# PT_2015_DB_MAIN_Rev1.net
KiCad netlist of a schematic drawn in EAGLE
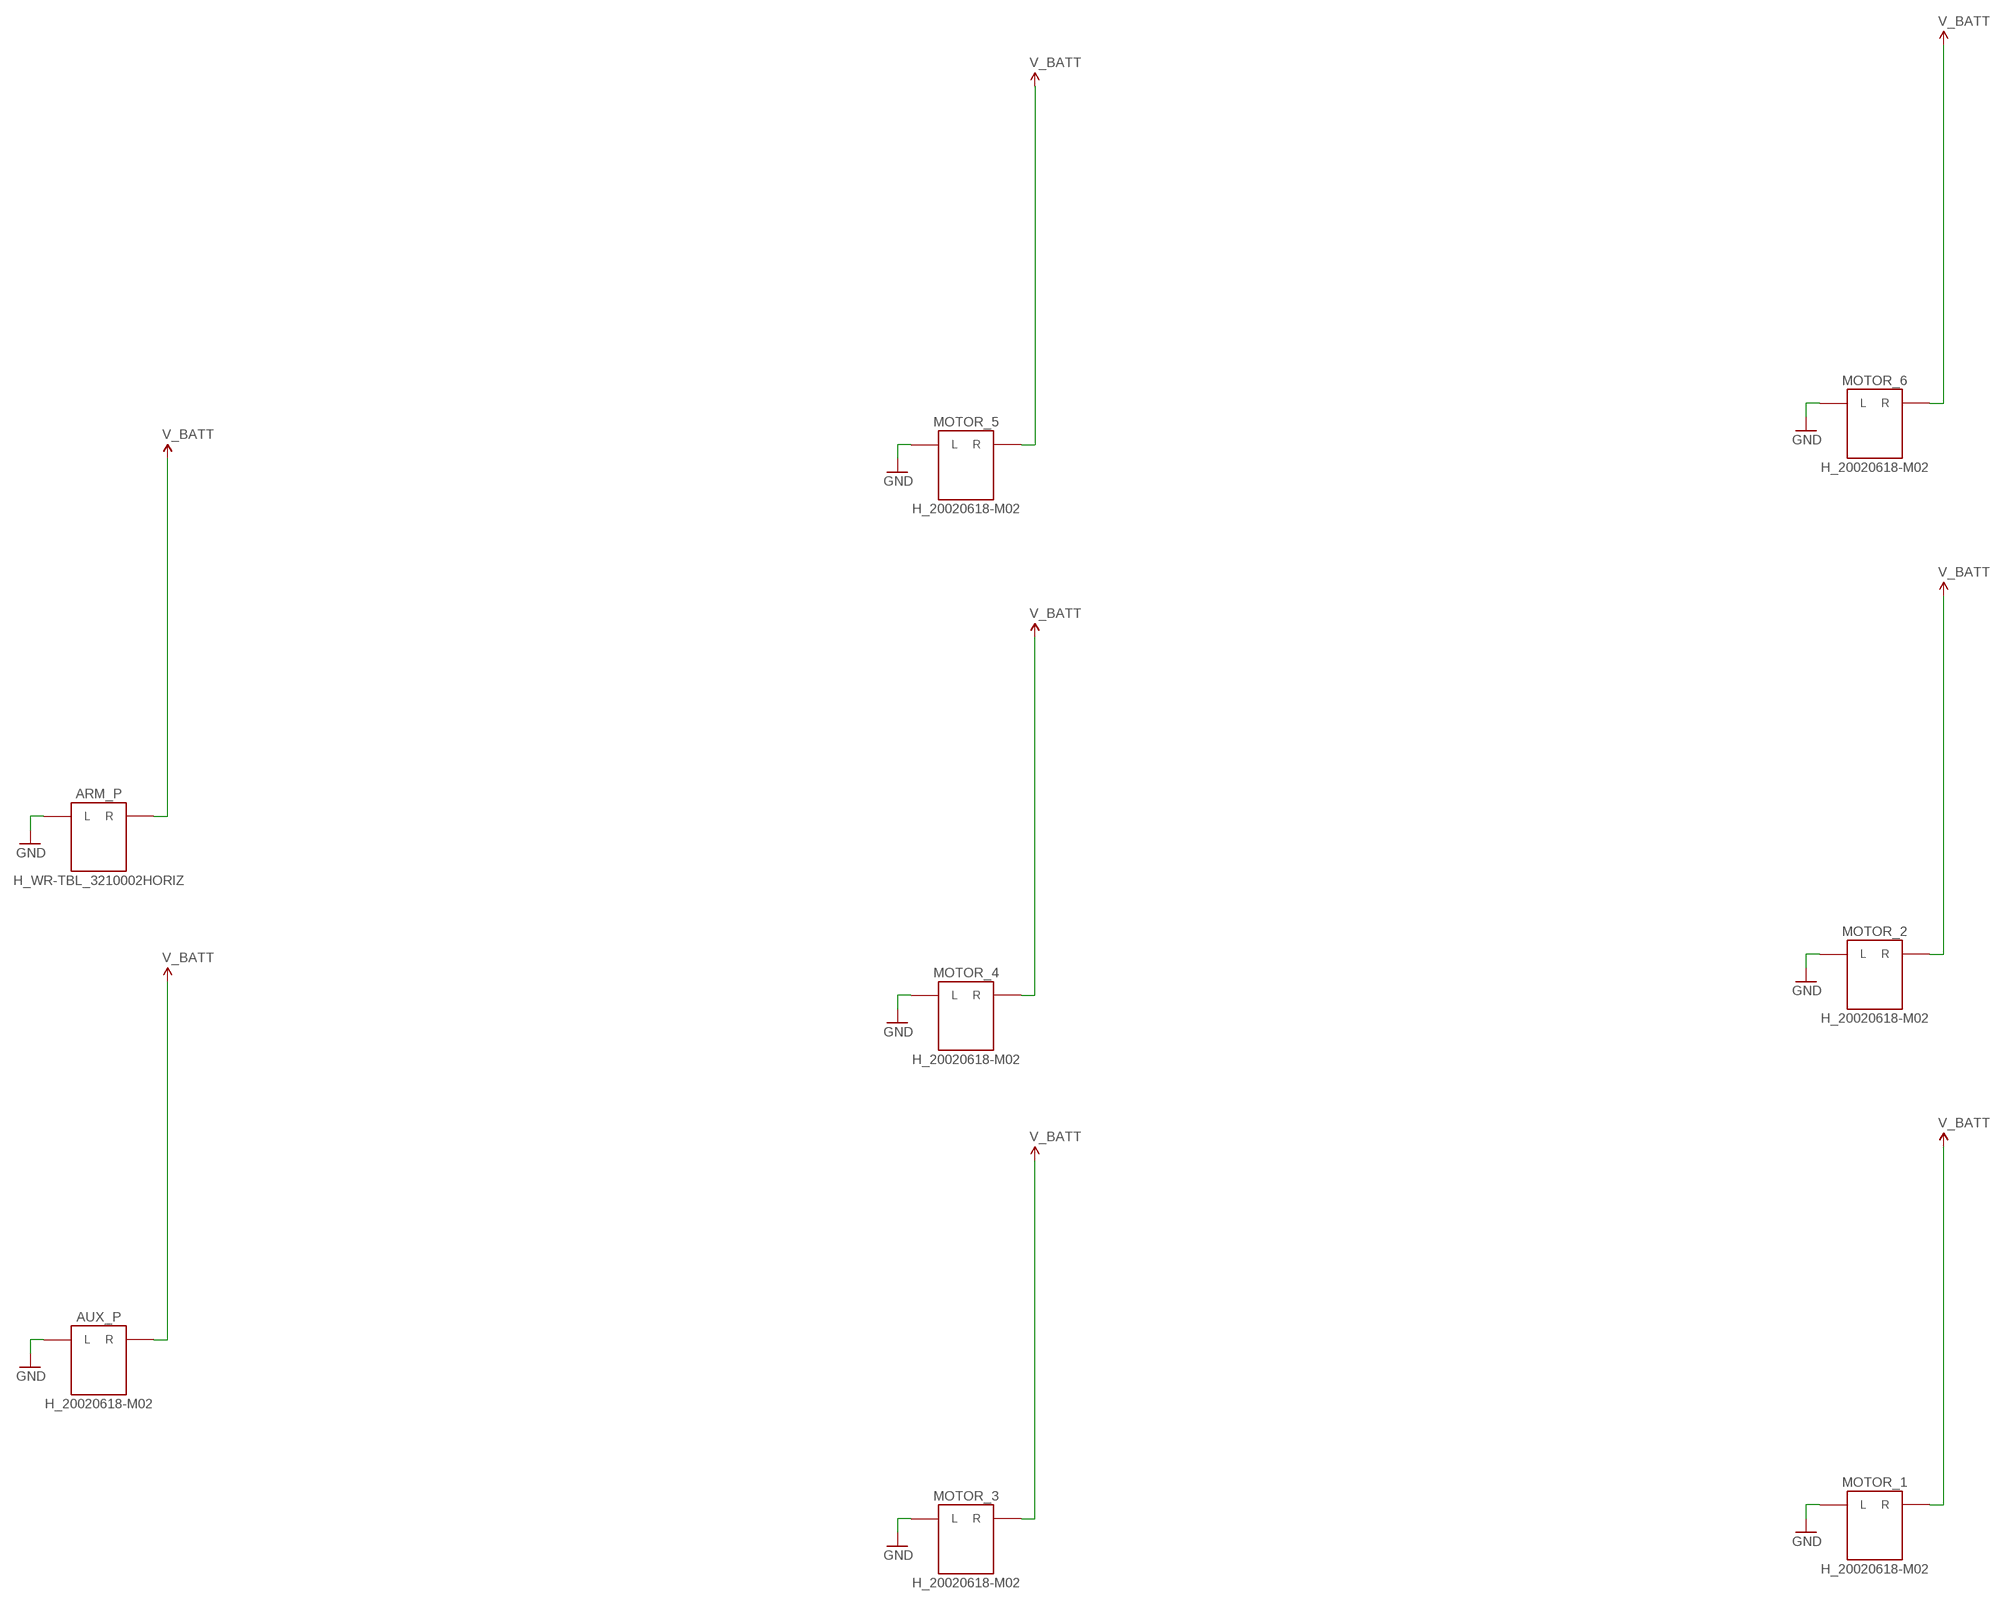
[diagram p0: schematic, sheet 1, part 1 of 2]
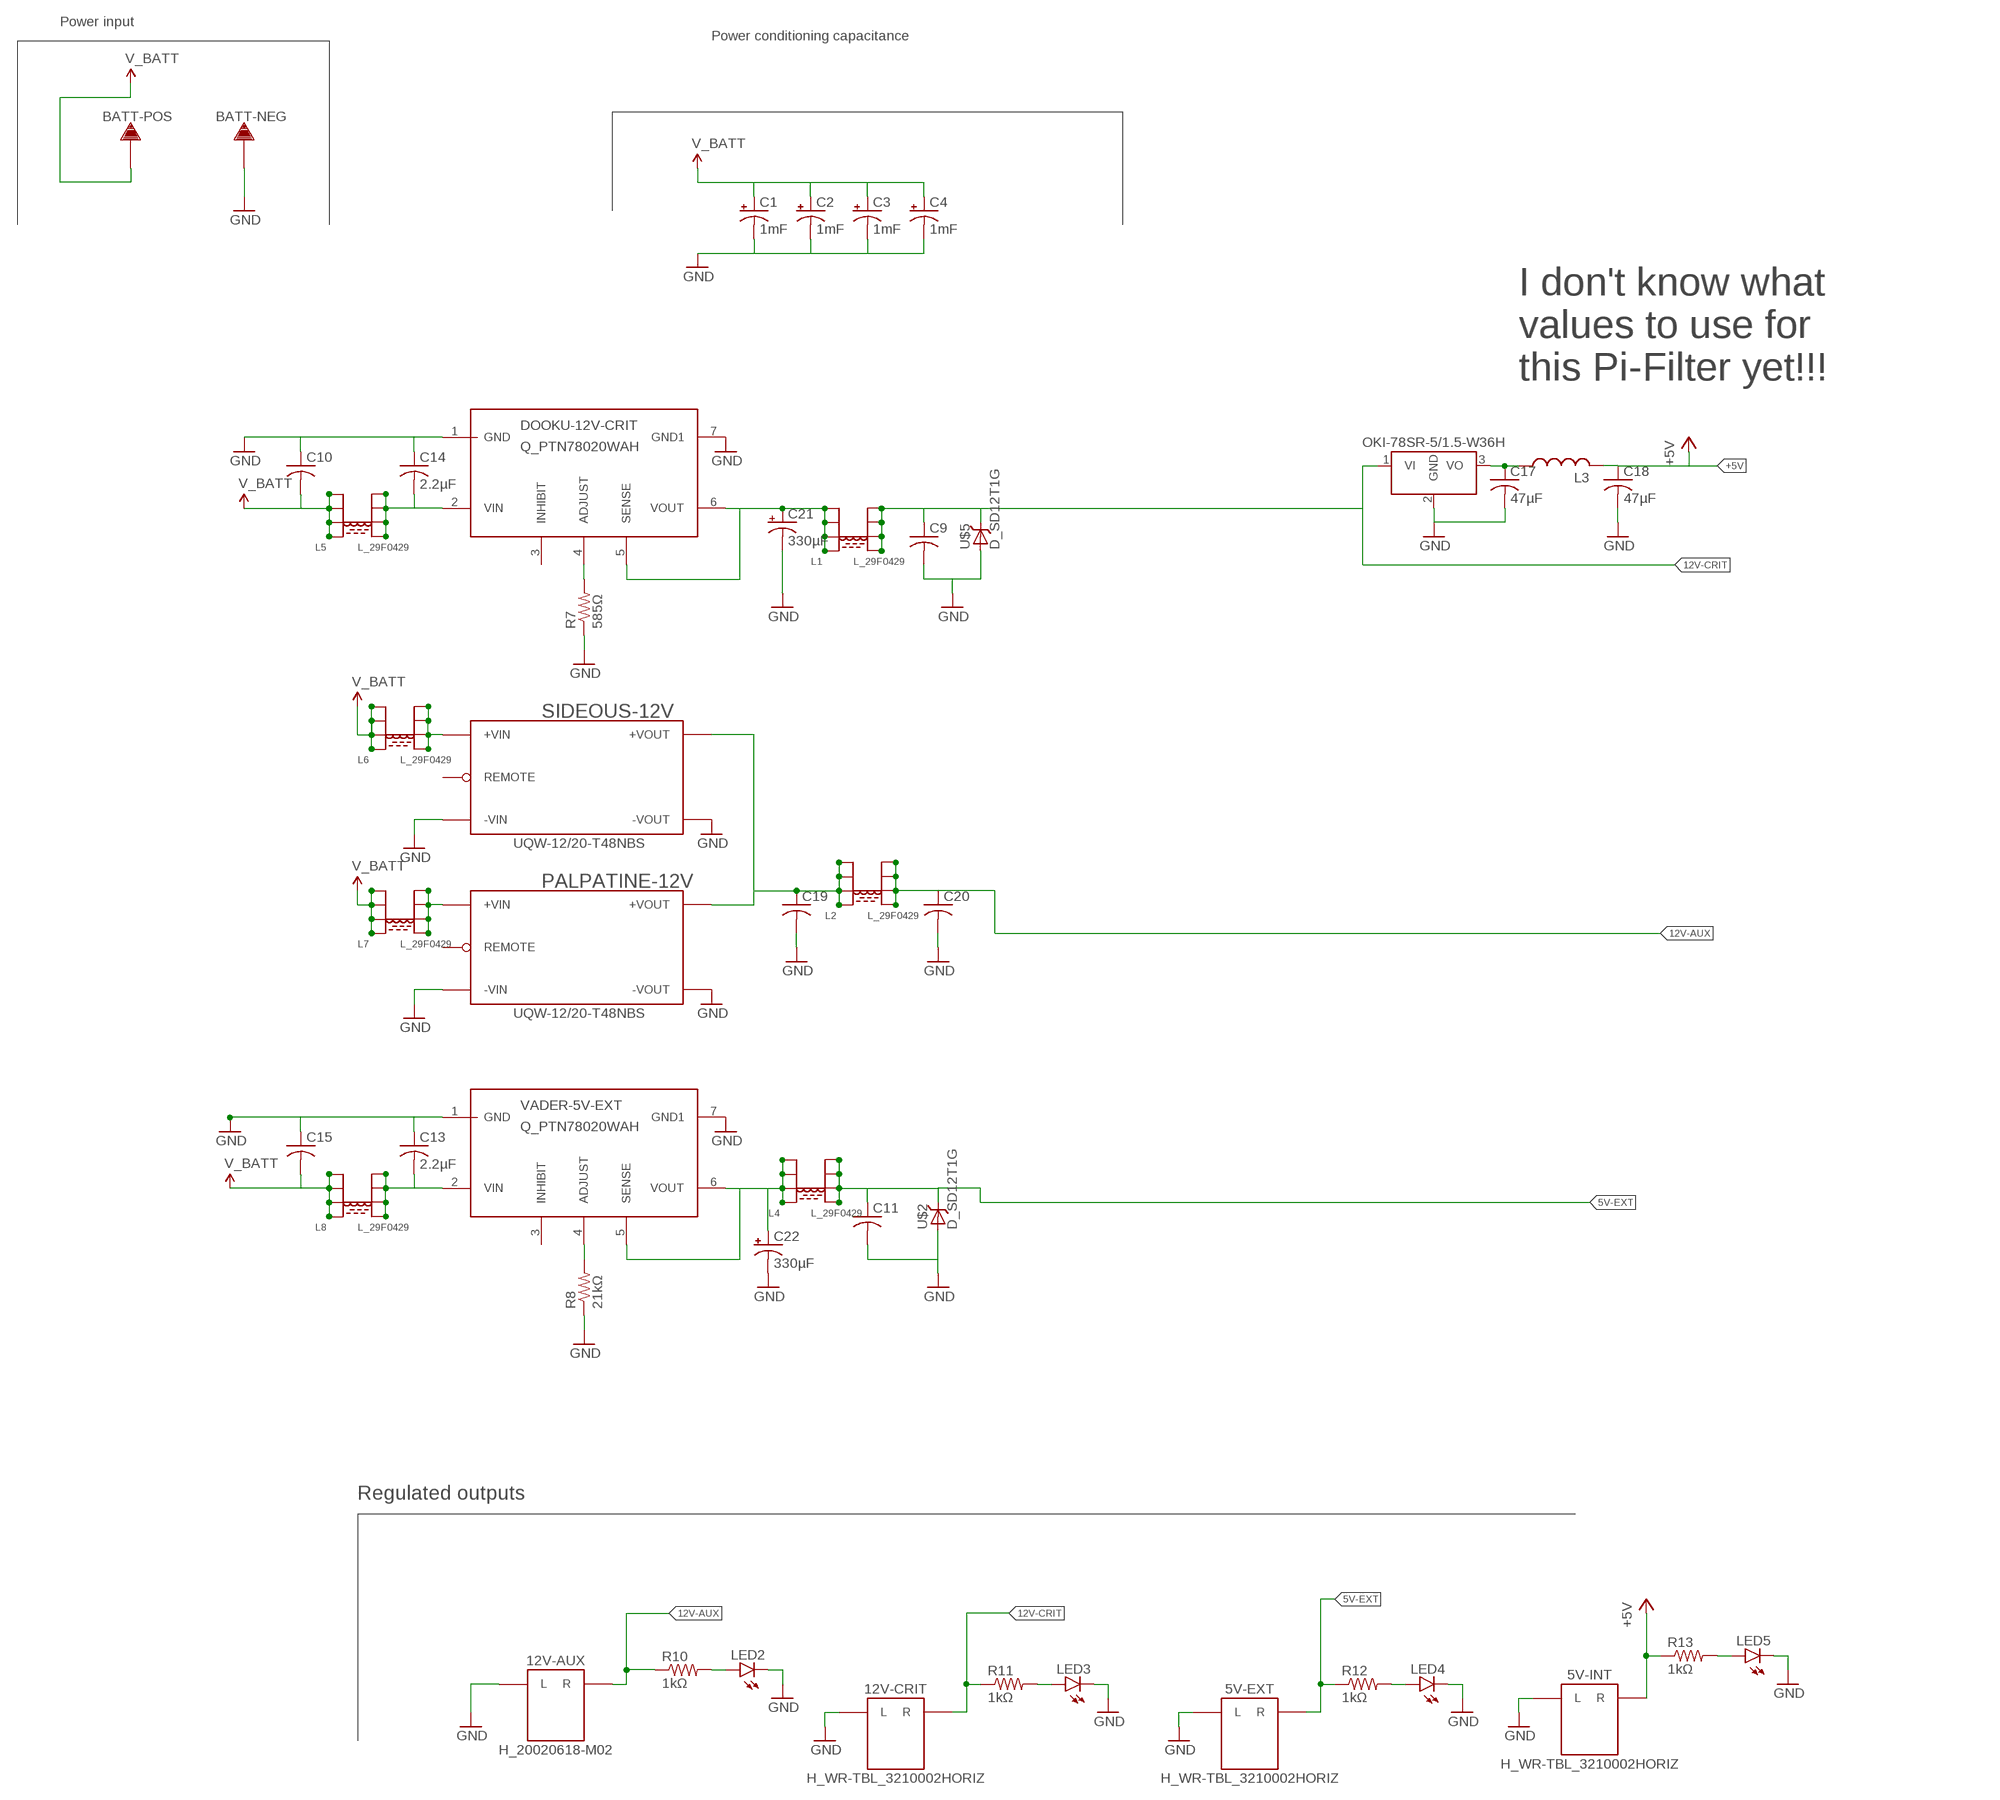
[diagram p1: schematic, sheet 1, part 2 of 2]

(export (version "E")
  (design (tool "Eeschema 10.0.6"))
  (components
    (comp (ref "5V-EXT")
      (value "H_WR-TBL_3210002HORIZ")
      (footprint "eagle-import:691322110002")
      (libsource (lib "eagle-import") (part "H_WR-TBL_3210002HORIZ"))
    )
    (comp (ref "5V-INT")
      (value "H_WR-TBL_3210002HORIZ")
      (footprint "eagle-import:691322110002")
      (libsource (lib "eagle-import") (part "H_WR-TBL_3210002HORIZ"))
    )
    (comp (ref "12V-AUX")
      (value "H_20020618-M02")
      (footprint "eagle-import:20020618-M02")
      (libsource (lib "eagle-import") (part "H_20020618-M02"))
    )
    (comp (ref "12V-CRIT")
      (value "H_WR-TBL_3210002HORIZ")
      (footprint "eagle-import:691322110002")
      (libsource (lib "eagle-import") (part "H_WR-TBL_3210002HORIZ"))
    )
    (comp (ref "ARM_P")
      (value "H_WR-TBL_3210002HORIZ")
      (footprint "eagle-import:691322110002")
      (libsource (lib "eagle-import") (part "H_WR-TBL_3210002HORIZ"))
    )
    (comp (ref "AUX_P")
      (value "H_20020618-M02")
      (footprint "eagle-import:20020618-M02")
      (libsource (lib "eagle-import") (part "H_20020618-M02"))
    )
    (comp (ref "BATT-NEG")
      (value "TERMINAL_HOLE")
      (footprint "eagle-import:LARGE_TERMINAL_HOLE")
      (libsource (lib "eagle-import") (part "TERMINAL_HOLE"))
    )
    (comp (ref "BATT-POS")
      (value "TERMINAL_HOLE")
      (footprint "eagle-import:LARGE_TERMINAL_HOLE")
      (libsource (lib "eagle-import") (part "TERMINAL_HOLE"))
    )
    (comp (ref "C1")
      (value "1mF")
      (footprint "eagle-import:C_12.5MM")
      (libsource (lib "eagle-import") (part "C_POL12.5MM_NORMAL"))
    )
    (comp (ref "C2")
      (value "1mF")
      (footprint "eagle-import:C_12.5MM")
      (libsource (lib "eagle-import") (part "C_POL12.5MM_NORMAL"))
    )
    (comp (ref "C3")
      (value "1mF")
      (footprint "eagle-import:C_12.5MM")
      (libsource (lib "eagle-import") (part "C_POL12.5MM_NORMAL"))
    )
    (comp (ref "C4")
      (value "1mF")
      (footprint "eagle-import:C_12.5MM")
      (libsource (lib "eagle-import") (part "C_POL12.5MM_NORMAL"))
    )
    (comp (ref "C9")
      (value "C-USC1206")
      (footprint "eagle-import:C1206")
      (libsource (lib "eagle-import") (part "C-USC1206"))
    )
    (comp (ref "C10")
      (value "C-USC1206")
      (footprint "eagle-import:C1206")
      (libsource (lib "eagle-import") (part "C-USC1206"))
    )
    (comp (ref "C11")
      (value "C-USC1206")
      (footprint "eagle-import:C1206")
      (libsource (lib "eagle-import") (part "C-USC1206"))
    )
    (comp (ref "C13")
      (value "2.2µF")
      (footprint "eagle-import:C1206")
      (libsource (lib "eagle-import") (part "C-USC1206"))
    )
    (comp (ref "C14")
      (value "2.2µF")
      (footprint "eagle-import:C1206")
      (libsource (lib "eagle-import") (part "C-USC1206"))
    )
    (comp (ref "C15")
      (value "C-USC1206")
      (footprint "eagle-import:C1206")
      (libsource (lib "eagle-import") (part "C-USC1206"))
    )
    (comp (ref "C17")
      (value "47µF")
      (footprint "eagle-import:C1206")
      (libsource (lib "eagle-import") (part "C-USC1206"))
    )
    (comp (ref "C18")
      (value "47µF")
      (footprint "eagle-import:C1206")
      (libsource (lib "eagle-import") (part "C-USC1206"))
    )
    (comp (ref "C19")
      (value "C-USC1206")
      (footprint "eagle-import:C1206")
      (libsource (lib "eagle-import") (part "C-USC1206"))
    )
    (comp (ref "C20")
      (value "C-USC1206")
      (footprint "eagle-import:C1206")
      (libsource (lib "eagle-import") (part "C-USC1206"))
    )
    (comp (ref "C21")
      (value "330µF")
      (footprint "eagle-import:E5-8,5")
      (libsource (lib "eagle-import") (part "CPOL-USE5-8.5"))
    )
    (comp (ref "C22")
      (value "330µF")
      (footprint "eagle-import:E5-8,5")
      (libsource (lib "eagle-import") (part "CPOL-USE5-8.5"))
    )
    (comp (ref "DOOKU-12V-CRIT")
      (value "Q_PTN78020WAH")
      (footprint "eagle-import:R_PDSS-T7")
      (libsource (lib "eagle-import") (part "Q_PTN78020"))
    )
    (comp (ref "L1")
      (value "L_29F0429")
      (footprint "eagle-import:L_29F0429")
      (libsource (lib "eagle-import") (part "L_29F0429"))
    )
    (comp (ref "L2")
      (value "L_29F0429")
      (footprint "eagle-import:L_29F0429")
      (libsource (lib "eagle-import") (part "L_29F0429"))
    )
    (comp (ref "L3")
      (value "L-USL3216C")
      (footprint "eagle-import:L3216C")
      (libsource (lib "eagle-import") (part "L-USL3216C"))
    )
    (comp (ref "L4")
      (value "L_29F0429")
      (footprint "eagle-import:L_29F0429")
      (libsource (lib "eagle-import") (part "L_29F0429"))
    )
    (comp (ref "L5")
      (value "L_29F0429")
      (footprint "eagle-import:L_29F0429")
      (libsource (lib "eagle-import") (part "L_29F0429"))
    )
    (comp (ref "L6")
      (value "L_29F0429")
      (footprint "eagle-import:L_29F0429")
      (libsource (lib "eagle-import") (part "L_29F0429"))
    )
    (comp (ref "L7")
      (value "L_29F0429")
      (footprint "eagle-import:L_29F0429")
      (libsource (lib "eagle-import") (part "L_29F0429"))
    )
    (comp (ref "L8")
      (value "L_29F0429")
      (footprint "eagle-import:L_29F0429")
      (libsource (lib "eagle-import") (part "L_29F0429"))
    )
    (comp (ref "LED2")
      (value "LED1206")
      (footprint "eagle-import:LED-1206")
      (libsource (lib "eagle-import") (part "LED1206"))
    )
    (comp (ref "LED3")
      (value "LED1206")
      (footprint "eagle-import:LED-1206")
      (libsource (lib "eagle-import") (part "LED1206"))
    )
    (comp (ref "LED4")
      (value "LED1206")
      (footprint "eagle-import:LED-1206")
      (libsource (lib "eagle-import") (part "LED1206"))
    )
    (comp (ref "LED5")
      (value "LED1206")
      (footprint "eagle-import:LED-1206")
      (libsource (lib "eagle-import") (part "LED1206"))
    )
    (comp (ref "MOTOR_1")
      (value "H_20020618-M02")
      (footprint "eagle-import:20020618-M02")
      (libsource (lib "eagle-import") (part "H_20020618-M02"))
    )
    (comp (ref "MOTOR_2")
      (value "H_20020618-M02")
      (footprint "eagle-import:20020618-M02")
      (libsource (lib "eagle-import") (part "H_20020618-M02"))
    )
    (comp (ref "MOTOR_3")
      (value "H_20020618-M02")
      (footprint "eagle-import:20020618-M02")
      (libsource (lib "eagle-import") (part "H_20020618-M02"))
    )
    (comp (ref "MOTOR_4")
      (value "H_20020618-M02")
      (footprint "eagle-import:20020618-M02")
      (libsource (lib "eagle-import") (part "H_20020618-M02"))
    )
    (comp (ref "MOTOR_5")
      (value "H_20020618-M02")
      (footprint "eagle-import:20020618-M02")
      (libsource (lib "eagle-import") (part "H_20020618-M02"))
    )
    (comp (ref "MOTOR_6")
      (value "H_20020618-M02")
      (footprint "eagle-import:20020618-M02")
      (libsource (lib "eagle-import") (part "H_20020618-M02"))
    )
    (comp (ref "OKI-78SR-5/1.5-W36H")
      (value "Q_OKI-78SR")
      (footprint "eagle-import:OKI-78SRH")
      (libsource (lib "eagle-import") (part "Q_OKI-78SR"))
    )
    (comp (ref "PALPATINE-12V")
      (value "UQW-12/20-T48NBS")
      (footprint "eagle-import:U-T48-QB-NO_TRIM")
      (libsource (lib "eagle-import") (part "UQW-12/20-T48NBS"))
    )
    (comp (ref "R7")
      (value "585Ω")
      (footprint "eagle-import:R1206")
      (libsource (lib "eagle-import") (part "R-US_R1206"))
    )
    (comp (ref "R8")
      (value "21kΩ")
      (footprint "eagle-import:R1206")
      (libsource (lib "eagle-import") (part "R-US_R1206"))
    )
    (comp (ref "R10")
      (value "1kΩ")
      (footprint "eagle-import:1206")
      (libsource (lib "eagle-import") (part "RESISTOR1206"))
    )
    (comp (ref "R11")
      (value "1kΩ")
      (footprint "eagle-import:1206")
      (libsource (lib "eagle-import") (part "RESISTOR1206"))
    )
    (comp (ref "R12")
      (value "1kΩ")
      (footprint "eagle-import:1206")
      (libsource (lib "eagle-import") (part "RESISTOR1206"))
    )
    (comp (ref "R13")
      (value "1kΩ")
      (footprint "eagle-import:1206")
      (libsource (lib "eagle-import") (part "RESISTOR1206"))
    )
    (comp (ref "SIDEOUS-12V")
      (value "UQW-12/20-T48NBS")
      (footprint "eagle-import:U-T48-QB-NO_TRIM")
      (libsource (lib "eagle-import") (part "UQW-12/20-T48NBS"))
    )
    (comp (ref "U$2")
      (value "D_SD12T1G")
      (footprint "eagle-import:SOD-323")
      (libsource (lib "eagle-import") (part "D_SD12T1G"))
    )
    (comp (ref "U$5")
      (value "D_SD12T1G")
      (footprint "eagle-import:SOD-323")
      (libsource (lib "eagle-import") (part "D_SD12T1G"))
    )
    (comp (ref "VADER-5V-EXT")
      (value "Q_PTN78020WAH")
      (footprint "eagle-import:R_PDSS-T7")
      (libsource (lib "eagle-import") (part "Q_PTN78020"))
    )
  )
  (nets
    (net (code "1") (name "+5V") (class "Default")
      (node (ref "5V-INT") (pin "R") (pinfunction "R_R") (pintype "bidirectional"))
      (node (ref "C18") (pin "1") (pinfunction "1_1") (pintype "passive"))
      (node (ref "L3") (pin "2") (pinfunction "2_2") (pintype "passive"))
      (node (ref "R13") (pin "1") (pinfunction "1_1") (pintype "passive"))
    )
    (net (code "2") (name "5V-EXT") (class "Default")
      (node (ref "5V-EXT") (pin "R") (pinfunction "R_R") (pintype "bidirectional"))
      (node (ref "C11") (pin "1") (pinfunction "1_1") (pintype "passive"))
      (node (ref "L4") (pin "5") (pinfunction "5_5") (pintype "bidirectional"))
      (node (ref "L4") (pin "6") (pinfunction "6_6") (pintype "bidirectional"))
      (node (ref "L4") (pin "7") (pinfunction "7_7") (pintype "bidirectional"))
      (node (ref "L4") (pin "8") (pinfunction "8_8") (pintype "bidirectional"))
      (node (ref "R12") (pin "1") (pinfunction "1_1") (pintype "passive"))
      (node (ref "U$2") (pin "1") (pinfunction "C_1") (pintype "passive"))
    )
    (net (code "3") (name "12V-AUX") (class "Default")
      (node (ref "12V-AUX") (pin "R1") (pinfunction "R_R1") (pintype "bidirectional"))
      (node (ref "12V-AUX") (pin "R2") (pinfunction "R_R2") (pintype "bidirectional"))
      (node (ref "C20") (pin "1") (pinfunction "1_1") (pintype "passive"))
      (node (ref "L2") (pin "5") (pinfunction "5_5") (pintype "bidirectional"))
      (node (ref "L2") (pin "6") (pinfunction "6_6") (pintype "bidirectional"))
      (node (ref "L2") (pin "7") (pinfunction "7_7") (pintype "bidirectional"))
      (node (ref "L2") (pin "8") (pinfunction "8_8") (pintype "bidirectional"))
      (node (ref "R10") (pin "1") (pinfunction "1_1") (pintype "passive"))
    )
    (net (code "4") (name "12V-CRIT") (class "Default")
      (node (ref "12V-CRIT") (pin "R") (pinfunction "R_R") (pintype "bidirectional"))
      (node (ref "C9") (pin "1") (pinfunction "1_1") (pintype "passive"))
      (node (ref "L1") (pin "5") (pinfunction "5_5") (pintype "bidirectional"))
      (node (ref "L1") (pin "6") (pinfunction "6_6") (pintype "bidirectional"))
      (node (ref "L1") (pin "7") (pinfunction "7_7") (pintype "bidirectional"))
      (node (ref "L1") (pin "8") (pinfunction "8_8") (pintype "bidirectional"))
      (node (ref "OKI-78SR-5/1.5-W36H") (pin "1") (pinfunction "VI_1") (pintype "bidirectional"))
      (node (ref "R11") (pin "1") (pinfunction "1_1") (pintype "passive"))
      (node (ref "U$5") (pin "1") (pinfunction "C_1") (pintype "passive"))
    )
    (net (code "5") (name "GND") (class "Default")
      (node (ref "12V-AUX") (pin "L1") (pinfunction "L_L1") (pintype "bidirectional"))
      (node (ref "12V-AUX") (pin "L2") (pinfunction "L_L2") (pintype "bidirectional"))
      (node (ref "12V-CRIT") (pin "L") (pinfunction "L_L") (pintype "bidirectional"))
      (node (ref "5V-EXT") (pin "L") (pinfunction "L_L") (pintype "bidirectional"))
      (node (ref "5V-INT") (pin "L") (pinfunction "L_L") (pintype "bidirectional"))
      (node (ref "ARM_P") (pin "L") (pinfunction "L_L") (pintype "bidirectional"))
      (node (ref "AUX_P") (pin "L1") (pinfunction "L_L1") (pintype "bidirectional"))
      (node (ref "AUX_P") (pin "L2") (pinfunction "L_L2") (pintype "bidirectional"))
      (node (ref "BATT-NEG") (pin "P$1") (pinfunction "P$1_P$1") (pintype "bidirectional"))
      (node (ref "C1") (pin "-") (pinfunction "-_-") (pintype "passive"))
      (node (ref "C10") (pin "1") (pinfunction "1_1") (pintype "passive"))
      (node (ref "C11") (pin "2") (pinfunction "2_2") (pintype "passive"))
      (node (ref "C13") (pin "1") (pinfunction "1_1") (pintype "passive"))
      (node (ref "C14") (pin "1") (pinfunction "1_1") (pintype "passive"))
      (node (ref "C15") (pin "1") (pinfunction "1_1") (pintype "passive"))
      (node (ref "C17") (pin "2") (pinfunction "2_2") (pintype "passive"))
      (node (ref "C18") (pin "2") (pinfunction "2_2") (pintype "passive"))
      (node (ref "C19") (pin "2") (pinfunction "2_2") (pintype "passive"))
      (node (ref "C2") (pin "-") (pinfunction "-_-") (pintype "passive"))
      (node (ref "C20") (pin "2") (pinfunction "2_2") (pintype "passive"))
      (node (ref "C21") (pin "-") (pinfunction "-_-") (pintype "passive"))
      (node (ref "C22") (pin "-") (pinfunction "-_-") (pintype "passive"))
      (node (ref "C3") (pin "-") (pinfunction "-_-") (pintype "passive"))
      (node (ref "C4") (pin "-") (pinfunction "-_-") (pintype "passive"))
      (node (ref "C9") (pin "2") (pinfunction "2_2") (pintype "passive"))
      (node (ref "DOOKU-12V-CRIT") (pin "1") (pinfunction "GND_1") (pintype "bidirectional"))
      (node (ref "DOOKU-12V-CRIT") (pin "7") (pinfunction "GND1_7") (pintype "bidirectional"))
      (node (ref "LED2") (pin "C") (pinfunction "C_C") (pintype "passive"))
      (node (ref "LED3") (pin "C") (pinfunction "C_C") (pintype "passive"))
      (node (ref "LED4") (pin "C") (pinfunction "C_C") (pintype "passive"))
      (node (ref "LED5") (pin "C") (pinfunction "C_C") (pintype "passive"))
      (node (ref "MOTOR_1") (pin "L1") (pinfunction "L_L1") (pintype "bidirectional"))
      (node (ref "MOTOR_1") (pin "L2") (pinfunction "L_L2") (pintype "bidirectional"))
      (node (ref "MOTOR_2") (pin "L1") (pinfunction "L_L1") (pintype "bidirectional"))
      (node (ref "MOTOR_2") (pin "L2") (pinfunction "L_L2") (pintype "bidirectional"))
      (node (ref "MOTOR_3") (pin "L1") (pinfunction "L_L1") (pintype "bidirectional"))
      (node (ref "MOTOR_3") (pin "L2") (pinfunction "L_L2") (pintype "bidirectional"))
      (node (ref "MOTOR_4") (pin "L1") (pinfunction "L_L1") (pintype "bidirectional"))
      (node (ref "MOTOR_4") (pin "L2") (pinfunction "L_L2") (pintype "bidirectional"))
      (node (ref "MOTOR_5") (pin "L1") (pinfunction "L_L1") (pintype "bidirectional"))
      (node (ref "MOTOR_5") (pin "L2") (pinfunction "L_L2") (pintype "bidirectional"))
      (node (ref "MOTOR_6") (pin "L1") (pinfunction "L_L1") (pintype "bidirectional"))
      (node (ref "MOTOR_6") (pin "L2") (pinfunction "L_L2") (pintype "bidirectional"))
      (node (ref "OKI-78SR-5/1.5-W36H") (pin "2") (pinfunction "GND_2") (pintype "bidirectional"))
      (node (ref "PALPATINE-12V") (pin "3") (pinfunction "-VIN_3") (pintype "bidirectional"))
      (node (ref "PALPATINE-12V") (pin "4") (pinfunction "-VOUT_4") (pintype "bidirectional"))
      (node (ref "R7") (pin "1") (pinfunction "1_1") (pintype "passive"))
      (node (ref "R8") (pin "1") (pinfunction "1_1") (pintype "passive"))
      (node (ref "SIDEOUS-12V") (pin "3") (pinfunction "-VIN_3") (pintype "bidirectional"))
      (node (ref "SIDEOUS-12V") (pin "4") (pinfunction "-VOUT_4") (pintype "bidirectional"))
      (node (ref "U$2") (pin "2") (pinfunction "A_2") (pintype "passive"))
      (node (ref "U$5") (pin "2") (pinfunction "A_2") (pintype "passive"))
      (node (ref "VADER-5V-EXT") (pin "1") (pinfunction "GND_1") (pintype "bidirectional"))
      (node (ref "VADER-5V-EXT") (pin "7") (pinfunction "GND1_7") (pintype "bidirectional"))
    )
    (net (code "6") (name "Net-(DOOKU-12V-CRIT-ADJUST)") (class "Default")
      (node (ref "DOOKU-12V-CRIT") (pin "4") (pinfunction "ADJUST_4") (pintype "bidirectional"))
      (node (ref "R7") (pin "2") (pinfunction "2_2") (pintype "passive"))
    )
    (net (code "7") (name "Net-(DOOKU-12V-CRIT-SENSE)") (class "Default")
      (node (ref "C21") (pin "+") (pinfunction "+_+") (pintype "passive"))
      (node (ref "DOOKU-12V-CRIT") (pin "5") (pinfunction "SENSE_5") (pintype "bidirectional"))
      (node (ref "DOOKU-12V-CRIT") (pin "6") (pinfunction "VOUT_6") (pintype "bidirectional"))
      (node (ref "L1") (pin "1") (pinfunction "1_1") (pintype "bidirectional"))
      (node (ref "L1") (pin "2") (pinfunction "2_2") (pintype "bidirectional"))
      (node (ref "L1") (pin "3") (pinfunction "3_3") (pintype "bidirectional"))
      (node (ref "L1") (pin "4") (pinfunction "4_4") (pintype "bidirectional"))
    )
    (net (code "8") (name "Net-(DOOKU-12V-CRIT-VIN)") (class "Default")
      (node (ref "C14") (pin "2") (pinfunction "2_2") (pintype "passive"))
      (node (ref "DOOKU-12V-CRIT") (pin "2") (pinfunction "VIN_2") (pintype "bidirectional"))
      (node (ref "L5") (pin "5") (pinfunction "5_5") (pintype "bidirectional"))
      (node (ref "L5") (pin "6") (pinfunction "6_6") (pintype "bidirectional"))
      (node (ref "L5") (pin "7") (pinfunction "7_7") (pintype "bidirectional"))
      (node (ref "L5") (pin "8") (pinfunction "8_8") (pintype "bidirectional"))
    )
    (net (code "9") (name "Net-(LED2-PadA)") (class "Default")
      (node (ref "LED2") (pin "A") (pinfunction "A_A") (pintype "passive"))
      (node (ref "R10") (pin "2") (pinfunction "2_2") (pintype "passive"))
    )
    (net (code "10") (name "Net-(LED3-PadA)") (class "Default")
      (node (ref "LED3") (pin "A") (pinfunction "A_A") (pintype "passive"))
      (node (ref "R11") (pin "2") (pinfunction "2_2") (pintype "passive"))
    )
    (net (code "11") (name "Net-(LED4-PadA)") (class "Default")
      (node (ref "LED4") (pin "A") (pinfunction "A_A") (pintype "passive"))
      (node (ref "R12") (pin "2") (pinfunction "2_2") (pintype "passive"))
    )
    (net (code "12") (name "Net-(LED5-PadA)") (class "Default")
      (node (ref "LED5") (pin "A") (pinfunction "A_A") (pintype "passive"))
      (node (ref "R13") (pin "2") (pinfunction "2_2") (pintype "passive"))
    )
    (net (code "13") (name "Net-(OKI-78SR-5/1.5-W36H-VO)") (class "Default")
      (node (ref "C17") (pin "1") (pinfunction "1_1") (pintype "passive"))
      (node (ref "L3") (pin "1") (pinfunction "1_1") (pintype "passive"))
      (node (ref "OKI-78SR-5/1.5-W36H") (pin "3") (pinfunction "VO_3") (pintype "bidirectional"))
    )
    (net (code "14") (name "Net-(PALPATINE-12V-+VIN)") (class "Default")
      (node (ref "L7") (pin "5") (pinfunction "5_5") (pintype "bidirectional"))
      (node (ref "L7") (pin "6") (pinfunction "6_6") (pintype "bidirectional"))
      (node (ref "L7") (pin "7") (pinfunction "7_7") (pintype "bidirectional"))
      (node (ref "L7") (pin "8") (pinfunction "8_8") (pintype "bidirectional"))
      (node (ref "PALPATINE-12V") (pin "1") (pinfunction "+VIN_1") (pintype "bidirectional"))
    )
    (net (code "15") (name "Net-(PALPATINE-12V-+VOUT)") (class "Default")
      (node (ref "C19") (pin "1") (pinfunction "1_1") (pintype "passive"))
      (node (ref "L2") (pin "1") (pinfunction "1_1") (pintype "bidirectional"))
      (node (ref "L2") (pin "2") (pinfunction "2_2") (pintype "bidirectional"))
      (node (ref "L2") (pin "3") (pinfunction "3_3") (pintype "bidirectional"))
      (node (ref "L2") (pin "4") (pinfunction "4_4") (pintype "bidirectional"))
      (node (ref "PALPATINE-12V") (pin "8") (pinfunction "+VOUT_8") (pintype "bidirectional"))
      (node (ref "SIDEOUS-12V") (pin "8") (pinfunction "+VOUT_8") (pintype "bidirectional"))
    )
    (net (code "16") (name "Net-(SIDEOUS-12V-+VIN)") (class "Default")
      (node (ref "L6") (pin "5") (pinfunction "5_5") (pintype "bidirectional"))
      (node (ref "L6") (pin "6") (pinfunction "6_6") (pintype "bidirectional"))
      (node (ref "L6") (pin "7") (pinfunction "7_7") (pintype "bidirectional"))
      (node (ref "L6") (pin "8") (pinfunction "8_8") (pintype "bidirectional"))
      (node (ref "SIDEOUS-12V") (pin "1") (pinfunction "+VIN_1") (pintype "bidirectional"))
    )
    (net (code "17") (name "Net-(VADER-5V-EXT-ADJUST)") (class "Default")
      (node (ref "R8") (pin "2") (pinfunction "2_2") (pintype "passive"))
      (node (ref "VADER-5V-EXT") (pin "4") (pinfunction "ADJUST_4") (pintype "bidirectional"))
    )
    (net (code "18") (name "Net-(VADER-5V-EXT-SENSE)") (class "Default")
      (node (ref "C22") (pin "+") (pinfunction "+_+") (pintype "passive"))
      (node (ref "L4") (pin "1") (pinfunction "1_1") (pintype "bidirectional"))
      (node (ref "L4") (pin "2") (pinfunction "2_2") (pintype "bidirectional"))
      (node (ref "L4") (pin "3") (pinfunction "3_3") (pintype "bidirectional"))
      (node (ref "L4") (pin "4") (pinfunction "4_4") (pintype "bidirectional"))
      (node (ref "VADER-5V-EXT") (pin "5") (pinfunction "SENSE_5") (pintype "bidirectional"))
      (node (ref "VADER-5V-EXT") (pin "6") (pinfunction "VOUT_6") (pintype "bidirectional"))
    )
    (net (code "19") (name "Net-(VADER-5V-EXT-VIN)") (class "Default")
      (node (ref "C13") (pin "2") (pinfunction "2_2") (pintype "passive"))
      (node (ref "L8") (pin "5") (pinfunction "5_5") (pintype "bidirectional"))
      (node (ref "L8") (pin "6") (pinfunction "6_6") (pintype "bidirectional"))
      (node (ref "L8") (pin "7") (pinfunction "7_7") (pintype "bidirectional"))
      (node (ref "L8") (pin "8") (pinfunction "8_8") (pintype "bidirectional"))
      (node (ref "VADER-5V-EXT") (pin "2") (pinfunction "VIN_2") (pintype "bidirectional"))
    )
    (net (code "20") (name "V_BATT") (class "Default")
      (node (ref "ARM_P") (pin "R") (pinfunction "R_R") (pintype "bidirectional"))
      (node (ref "AUX_P") (pin "R1") (pinfunction "R_R1") (pintype "bidirectional"))
      (node (ref "AUX_P") (pin "R2") (pinfunction "R_R2") (pintype "bidirectional"))
      (node (ref "BATT-POS") (pin "P$1") (pinfunction "P$1_P$1") (pintype "bidirectional"))
      (node (ref "C1") (pin "+") (pinfunction "+_+") (pintype "passive"))
      (node (ref "C10") (pin "2") (pinfunction "2_2") (pintype "passive"))
      (node (ref "C15") (pin "2") (pinfunction "2_2") (pintype "passive"))
      (node (ref "C2") (pin "+") (pinfunction "+_+") (pintype "passive"))
      (node (ref "C3") (pin "+") (pinfunction "+_+") (pintype "passive"))
      (node (ref "C4") (pin "+") (pinfunction "+_+") (pintype "passive"))
      (node (ref "L5") (pin "1") (pinfunction "1_1") (pintype "bidirectional"))
      (node (ref "L5") (pin "2") (pinfunction "2_2") (pintype "bidirectional"))
      (node (ref "L5") (pin "3") (pinfunction "3_3") (pintype "bidirectional"))
      (node (ref "L5") (pin "4") (pinfunction "4_4") (pintype "bidirectional"))
      (node (ref "L6") (pin "1") (pinfunction "1_1") (pintype "bidirectional"))
      (node (ref "L6") (pin "2") (pinfunction "2_2") (pintype "bidirectional"))
      (node (ref "L6") (pin "3") (pinfunction "3_3") (pintype "bidirectional"))
      (node (ref "L6") (pin "4") (pinfunction "4_4") (pintype "bidirectional"))
      (node (ref "L7") (pin "1") (pinfunction "1_1") (pintype "bidirectional"))
      (node (ref "L7") (pin "2") (pinfunction "2_2") (pintype "bidirectional"))
      (node (ref "L7") (pin "3") (pinfunction "3_3") (pintype "bidirectional"))
      (node (ref "L7") (pin "4") (pinfunction "4_4") (pintype "bidirectional"))
      (node (ref "L8") (pin "1") (pinfunction "1_1") (pintype "bidirectional"))
      (node (ref "L8") (pin "2") (pinfunction "2_2") (pintype "bidirectional"))
      (node (ref "L8") (pin "3") (pinfunction "3_3") (pintype "bidirectional"))
      (node (ref "L8") (pin "4") (pinfunction "4_4") (pintype "bidirectional"))
      (node (ref "MOTOR_1") (pin "R1") (pinfunction "R_R1") (pintype "bidirectional"))
      (node (ref "MOTOR_1") (pin "R2") (pinfunction "R_R2") (pintype "bidirectional"))
      (node (ref "MOTOR_2") (pin "R1") (pinfunction "R_R1") (pintype "bidirectional"))
      (node (ref "MOTOR_2") (pin "R2") (pinfunction "R_R2") (pintype "bidirectional"))
      (node (ref "MOTOR_3") (pin "R1") (pinfunction "R_R1") (pintype "bidirectional"))
      (node (ref "MOTOR_3") (pin "R2") (pinfunction "R_R2") (pintype "bidirectional"))
      (node (ref "MOTOR_4") (pin "R1") (pinfunction "R_R1") (pintype "bidirectional"))
      (node (ref "MOTOR_4") (pin "R2") (pinfunction "R_R2") (pintype "bidirectional"))
      (node (ref "MOTOR_5") (pin "R1") (pinfunction "R_R1") (pintype "bidirectional"))
      (node (ref "MOTOR_5") (pin "R2") (pinfunction "R_R2") (pintype "bidirectional"))
      (node (ref "MOTOR_6") (pin "R1") (pinfunction "R_R1") (pintype "bidirectional"))
      (node (ref "MOTOR_6") (pin "R2") (pinfunction "R_R2") (pintype "bidirectional"))
    )
    (net (code "21") (name "unconnected-(DOOKU-12V-CRIT-INHIBIT-Pad3)") (class "Default")
      (node (ref "DOOKU-12V-CRIT") (pin "3") (pinfunction "INHIBIT_3") (pintype "bidirectional"))
    )
    (net (code "22") (name "unconnected-(PALPATINE-12V-REMOTE-Pad2)") (class "Default")
      (node (ref "PALPATINE-12V") (pin "2") (pinfunction "REMOTE_2") (pintype "bidirectional"))
    )
    (net (code "23") (name "unconnected-(SIDEOUS-12V-REMOTE-Pad2)") (class "Default")
      (node (ref "SIDEOUS-12V") (pin "2") (pinfunction "REMOTE_2") (pintype "bidirectional"))
    )
    (net (code "24") (name "unconnected-(VADER-5V-EXT-INHIBIT-Pad3)") (class "Default")
      (node (ref "VADER-5V-EXT") (pin "3") (pinfunction "INHIBIT_3") (pintype "bidirectional"))
    )
  )
)
